# Square8_V1_2.net
KiCad netlist of a schematic drawn in EAGLE
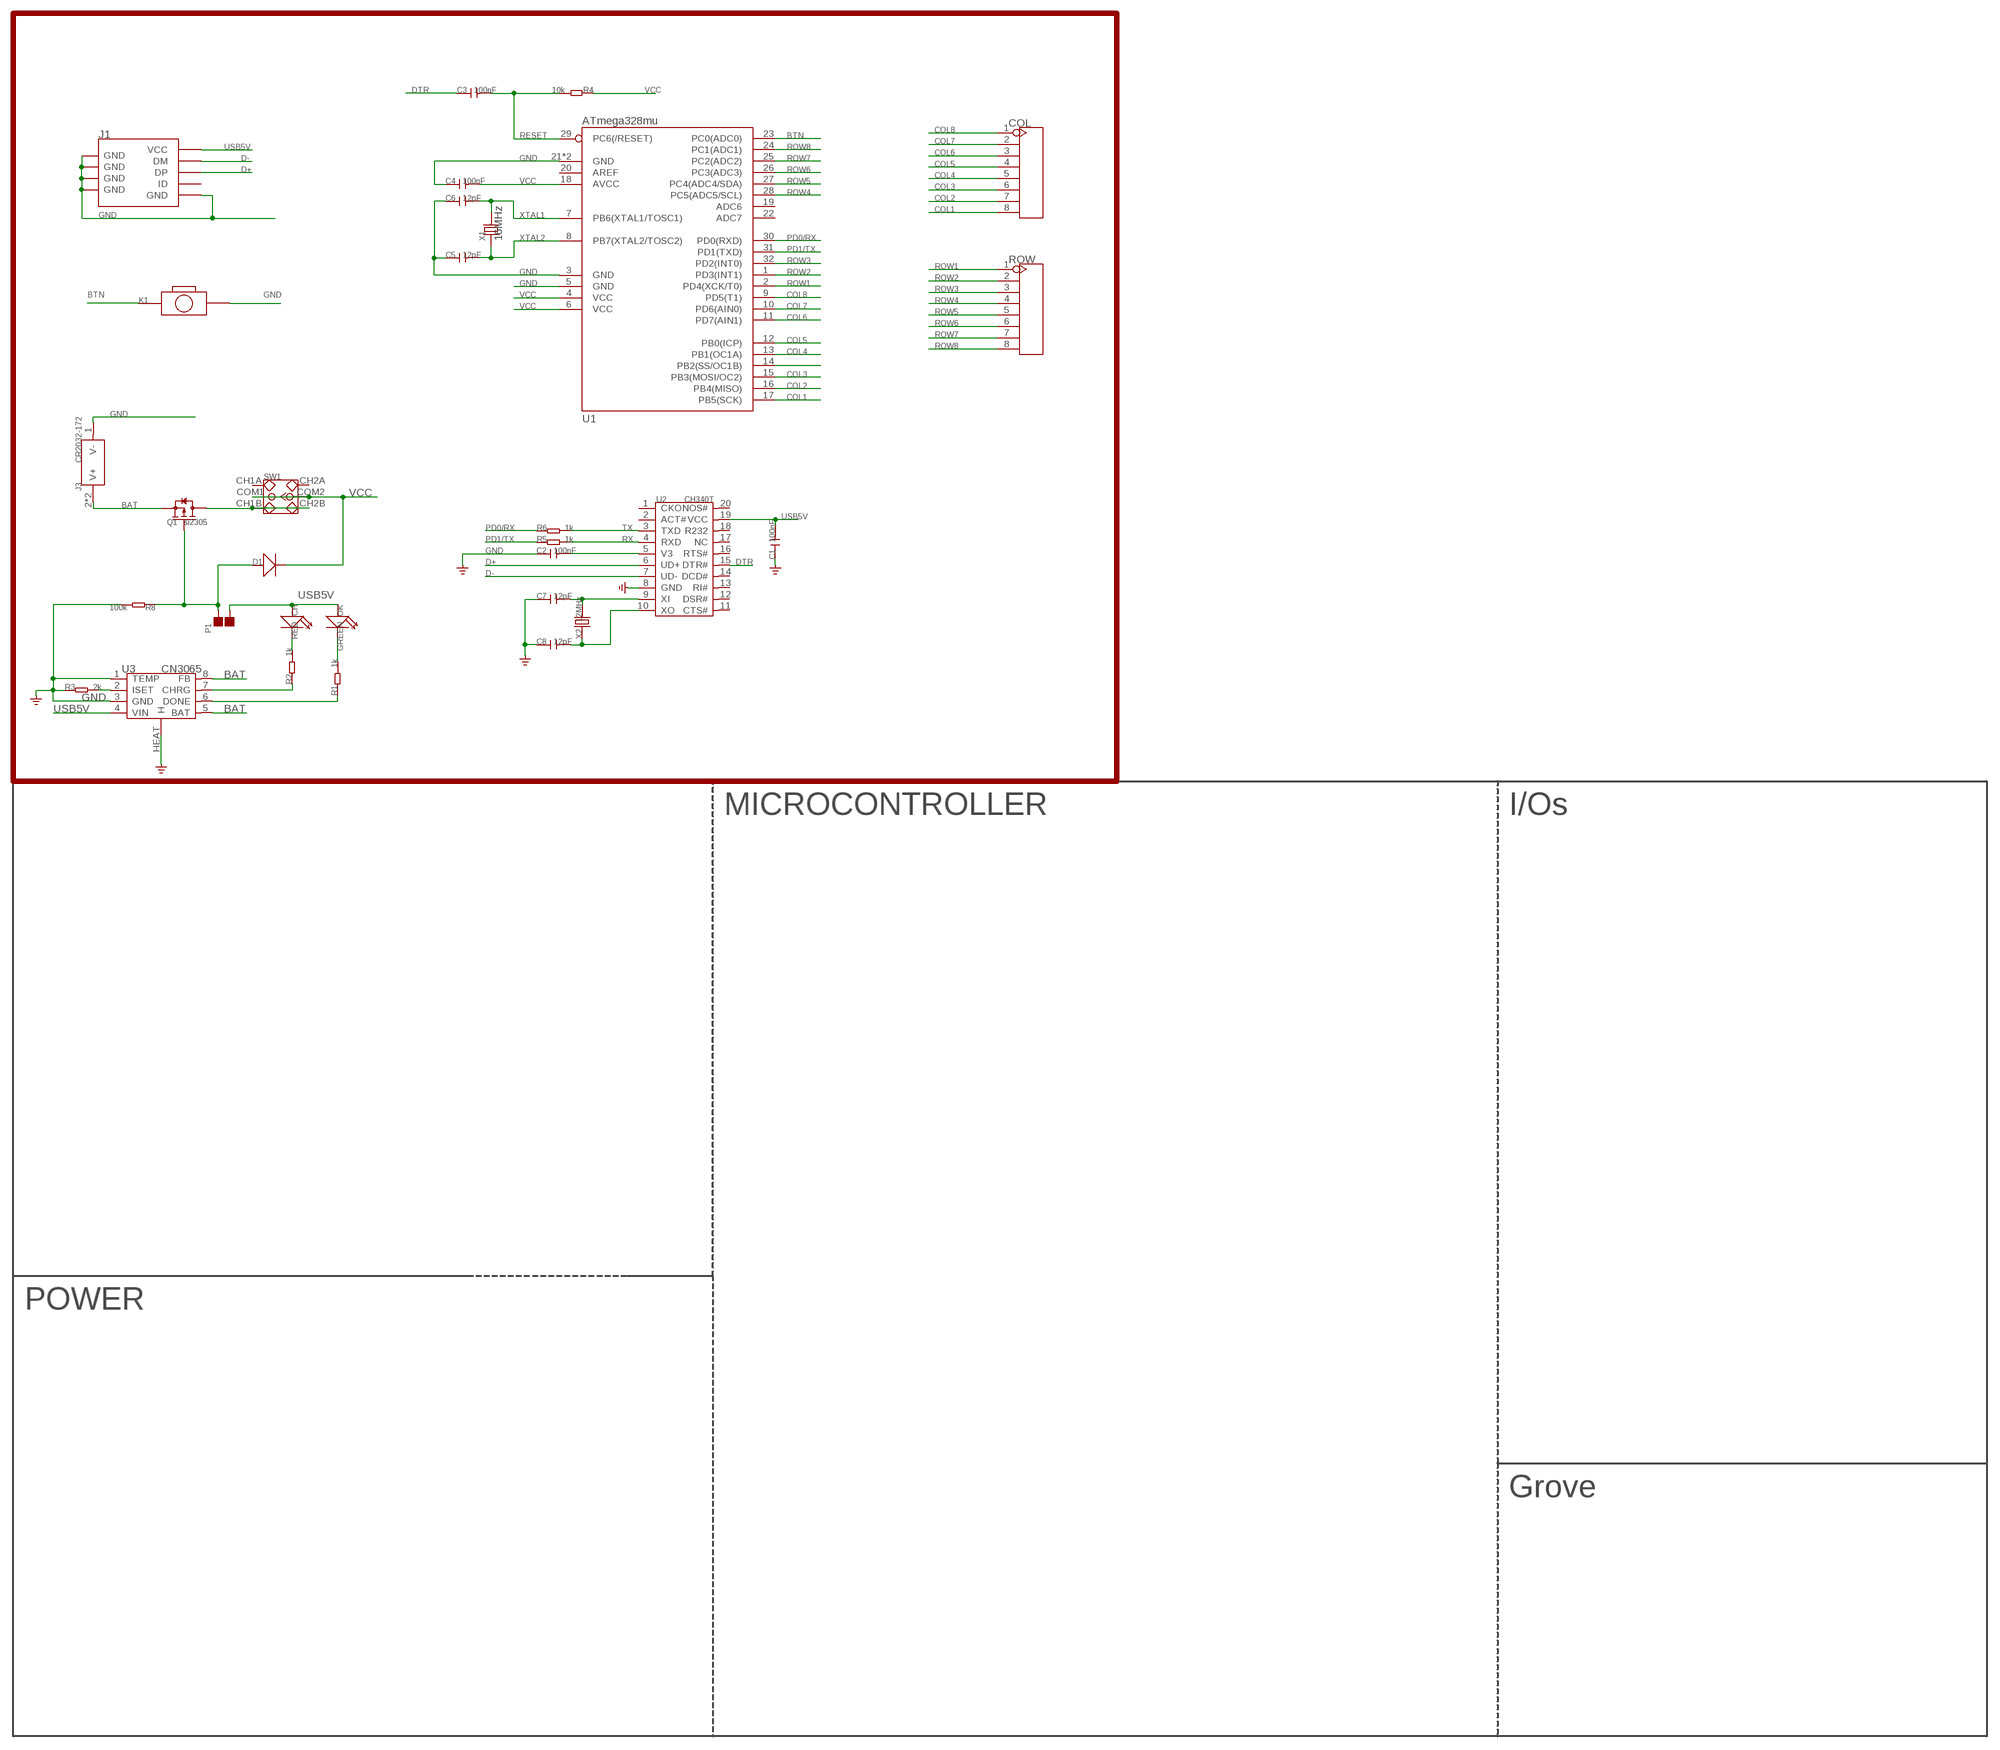
[diagram p0: schematic, sheet 1]

(export (version "E")
  (design (tool "Eeschema 10.0.6"))
  (components
    (comp (ref "C1")
      (value "100nF")
      (footprint "eagle-import:CERAMIC-2.54")
      (libsource (lib "eagle-import") (part "C'2.54'"))
    )
    (comp (ref "C2")
      (value "100nF")
      (footprint "eagle-import:CERAMIC-2.54")
      (libsource (lib "eagle-import") (part "C'2.54'"))
    )
    (comp (ref "C3")
      (value "100nF")
      (footprint "eagle-import:CERAMIC-2.54")
      (libsource (lib "eagle-import") (part "C'2.54'"))
    )
    (comp (ref "C4")
      (value "100nF")
      (footprint "eagle-import:CERAMIC-2.54")
      (libsource (lib "eagle-import") (part "C'2.54'"))
    )
    (comp (ref "C5")
      (value "12pF")
      (footprint "eagle-import:C0603")
      (libsource (lib "eagle-import") (part "C-0603"))
    )
    (comp (ref "C6")
      (value "12pF")
      (footprint "eagle-import:C0603")
      (libsource (lib "eagle-import") (part "C-0603"))
    )
    (comp (ref "C7")
      (value "12pF")
      (footprint "eagle-import:C0603")
      (libsource (lib "eagle-import") (part "C-0603"))
    )
    (comp (ref "C8")
      (value "12pF")
      (footprint "eagle-import:C0603")
      (libsource (lib "eagle-import") (part "C-0603"))
    )
    (comp (ref "CH")
      (value "RED")
      (footprint "eagle-import:LED-2P-2.54-3MM")
      (libsource (lib "eagle-import") (part "LED-3MM"))
    )
    (comp (ref "COL")
      (value "HEADER-8P-2.54")
      (footprint "eagle-import:8P-2.54")
      (libsource (lib "eagle-import") (part "HEADER-8P-2.54"))
    )
    (comp (ref "D1")
      (value "D'B130L-13-F'")
      (footprint "eagle-import:SMA")
      (libsource (lib "eagle-import") (part "D'B130L-13-F'"))
    )
    (comp (ref "J1")
      (value "USB-MINIUSB-5P-MICRO")
      (footprint "eagle-import:MICRO-USB")
      (libsource (lib "eagle-import") (part "USB-MINIUSB-5P-MICRO"))
    )
    (comp (ref "J3")
      (value "CR2032-172")
      (footprint "eagle-import:2032-D20-CIRCLE")
      (libsource (lib "eagle-import") (part "HOLDER-BAT-CIRCLE"))
    )
    (comp (ref "K1")
      (value "BUTTON-2P'TS-1101F'")
      (footprint "eagle-import:2P-3.4X6.0X3.55H-90D")
      (libsource (lib "eagle-import") (part "BUTTON-2P'TS-1101F'"))
    )
    (comp (ref "OK")
      (value "GREEN")
      (footprint "eagle-import:LED-2P-2.54-3MM")
      (libsource (lib "eagle-import") (part "LED-3MM"))
    )
    (comp (ref "P1")
      (value "PAD-JUMPER-2P")
      (footprint "eagle-import:2P-SMD-1.78X1.27")
      (fields (field (name "PARTNO") "DNP"))
      (libsource (lib "eagle-import") (part "PAD-JUMPER-2P"))
    )
    (comp (ref "Q1")
      (value "si2305")
      (footprint "eagle-import:SOT23")
      (libsource (lib "eagle-import") (part "MOSFET-P'SI2323CDS/SI2305DS{lt}BR{gt}'"))
    )
    (comp (ref "R1")
      (value "1k")
      (footprint "eagle-import:R0204_7")
      (libsource (lib "eagle-import") (part "R-0204/7"))
    )
    (comp (ref "R2")
      (value "1k")
      (footprint "eagle-import:R0204_7")
      (libsource (lib "eagle-import") (part "R-0204/7"))
    )
    (comp (ref "R3")
      (value "2k")
      (footprint "eagle-import:R0204_7")
      (libsource (lib "eagle-import") (part "R-0204/7"))
    )
    (comp (ref "R4")
      (value "10k")
      (footprint "eagle-import:R0204_7")
      (libsource (lib "eagle-import") (part "R-0204/7"))
    )
    (comp (ref "R5")
      (value "1k")
      (footprint "eagle-import:R0204_7")
      (libsource (lib "eagle-import") (part "R-0204/7"))
    )
    (comp (ref "R6")
      (value "1k")
      (footprint "eagle-import:R0204_7")
      (libsource (lib "eagle-import") (part "R-0204/7"))
    )
    (comp (ref "R8")
      (value "100k")
      (footprint "eagle-import:R0603")
      (libsource (lib "eagle-import") (part "R-0603"))
    )
    (comp (ref "ROW")
      (value "HEADER-8P-2.54")
      (footprint "eagle-import:8P-2.54")
      (libsource (lib "eagle-import") (part "HEADER-8P-2.54"))
    )
    (comp (ref "SW1")
      (value "SWITCH-2CH-6P'90D'")
      (footprint "eagle-import:6P-2CH-2.5-9.1X3.5X3.2H-90D")
      (libsource (lib "eagle-import") (part "SWITCH-2CH-6P'90D'"))
    )
    (comp (ref "U1")
      (value "ATmega328mu")
      (footprint "eagle-import:MLF32X-W_HEAT")
      (libsource (lib "eagle-import") (part "ATMEGA8/168/328MLF"))
    )
    (comp (ref "U2")
      (value "CH340T")
      (footprint "eagle-import:SSOP20")
      (libsource (lib "eagle-import") (part "CH340T"))
    )
    (comp (ref "U3")
      (value "CN3065")
      (footprint "eagle-import:DFN8")
      (libsource (lib "eagle-import") (part "CN3065"))
    )
    (comp (ref "X1")
      (value "16MHz")
      (footprint "eagle-import:HC49S")
      (libsource (lib "eagle-import") (part "CRYSTAL'HC49S'"))
    )
    (comp (ref "X2")
      (value "12MHz")
      (footprint "eagle-import:HC49S")
      (libsource (lib "eagle-import") (part "CRYSTAL'HC49S'"))
    )
  )
  (nets
    (net (code "1") (name "/BAT") (class "Default")
      (node (ref "J3") (pin "2") (pinfunction "V+_2") (pintype "bidirectional"))
      (node (ref "J3") (pin "3") (pinfunction "V+_3") (pintype "bidirectional"))
      (node (ref "Q1") (pin "2") (pinfunction "S_2") (pintype "passive"))
      (node (ref "U3") (pin "5") (pinfunction "BAT_5") (pintype "bidirectional"))
      (node (ref "U3") (pin "8") (pinfunction "FB_8") (pintype "input"))
    )
    (net (code "2") (name "/BTN") (class "Default")
      (node (ref "K1") (pin "P$1") (pinfunction "1_P$1") (pintype "bidirectional"))
      (node (ref "U1") (pin "23") (pinfunction "PC0(ADC0)_23") (pintype "bidirectional"))
    )
    (net (code "3") (name "/COL1") (class "Default")
      (node (ref "COL") (pin "8") (pinfunction "8_8") (pintype "bidirectional"))
      (node (ref "U1") (pin "17") (pinfunction "PB5(SCK)_17") (pintype "bidirectional"))
    )
    (net (code "4") (name "/COL2") (class "Default")
      (node (ref "COL") (pin "7") (pinfunction "7_7") (pintype "bidirectional"))
      (node (ref "U1") (pin "16") (pinfunction "PB4(MISO)_16") (pintype "bidirectional"))
    )
    (net (code "5") (name "/COL3") (class "Default")
      (node (ref "COL") (pin "6") (pinfunction "6_6") (pintype "bidirectional"))
      (node (ref "U1") (pin "15") (pinfunction "PB3(MOSI/OC2)_15") (pintype "bidirectional"))
    )
    (net (code "6") (name "/COL4") (class "Default")
      (node (ref "COL") (pin "5") (pinfunction "5_5") (pintype "bidirectional"))
      (node (ref "U1") (pin "13") (pinfunction "PB1(OC1A)_13") (pintype "bidirectional"))
    )
    (net (code "7") (name "/COL5") (class "Default")
      (node (ref "COL") (pin "4") (pinfunction "4_4") (pintype "bidirectional"))
      (node (ref "U1") (pin "12") (pinfunction "PB0(ICP)_12") (pintype "bidirectional"))
    )
    (net (code "8") (name "/COL6") (class "Default")
      (node (ref "COL") (pin "3") (pinfunction "3_3") (pintype "bidirectional"))
      (node (ref "U1") (pin "11") (pinfunction "PD7(AIN1)_11") (pintype "bidirectional"))
    )
    (net (code "9") (name "/COL7") (class "Default")
      (node (ref "COL") (pin "2") (pinfunction "2_2") (pintype "bidirectional"))
      (node (ref "U1") (pin "10") (pinfunction "PD6(AIN0)_10") (pintype "bidirectional"))
    )
    (net (code "10") (name "/COL8") (class "Default")
      (node (ref "COL") (pin "1") (pinfunction "1_1") (pintype "bidirectional"))
      (node (ref "U1") (pin "9") (pinfunction "PD5(T1)_9") (pintype "bidirectional"))
    )
    (net (code "11") (name "/D+") (class "Default")
      (node (ref "J1") (pin "3") (pinfunction "DP_3") (pintype "bidirectional"))
      (node (ref "U2") (pin "6") (pinfunction "UD+_6") (pintype "bidirectional"))
    )
    (net (code "12") (name "/D-") (class "Default")
      (node (ref "J1") (pin "2") (pinfunction "DM_2") (pintype "bidirectional"))
      (node (ref "U2") (pin "7") (pinfunction "UD-_7") (pintype "bidirectional"))
    )
    (net (code "13") (name "/DTR") (class "Default")
      (node (ref "C3") (pin "1") (pinfunction "1_1") (pintype "passive"))
      (node (ref "U2") (pin "15") (pinfunction "DTR#_15") (pintype "output"))
    )
    (net (code "14") (name "/NOS#") (class "Default")
      (node (ref "U2") (pin "20") (pinfunction "NOS#_20") (pintype "power_in"))
    )
    (net (code "15") (name "/PD0{slash}RX") (class "Default")
      (node (ref "R6") (pin "1") (pinfunction "1_1") (pintype "passive"))
      (node (ref "U1") (pin "30") (pinfunction "PD0(RXD)_30") (pintype "bidirectional"))
    )
    (net (code "16") (name "/PD1{slash}TX") (class "Default")
      (node (ref "R5") (pin "1") (pinfunction "1_1") (pintype "passive"))
      (node (ref "U1") (pin "31") (pinfunction "PD1(TXD)_31") (pintype "bidirectional"))
    )
    (net (code "17") (name "/RESET") (class "Default")
      (node (ref "C3") (pin "2") (pinfunction "2_2") (pintype "passive"))
      (node (ref "R4") (pin "2") (pinfunction "2_2") (pintype "passive"))
      (node (ref "U1") (pin "29") (pinfunction "PC6(/RESET)_29") (pintype "bidirectional"))
    )
    (net (code "18") (name "/ROW1") (class "Default")
      (node (ref "ROW") (pin "1") (pinfunction "1_1") (pintype "bidirectional"))
      (node (ref "U1") (pin "2") (pinfunction "PD4(XCK/T0)_2") (pintype "bidirectional"))
    )
    (net (code "19") (name "/ROW2") (class "Default")
      (node (ref "ROW") (pin "2") (pinfunction "2_2") (pintype "bidirectional"))
      (node (ref "U1") (pin "1") (pinfunction "PD3(INT1)_1") (pintype "bidirectional"))
    )
    (net (code "20") (name "/ROW3") (class "Default")
      (node (ref "ROW") (pin "3") (pinfunction "3_3") (pintype "bidirectional"))
      (node (ref "U1") (pin "32") (pinfunction "PD2(INT0)_32") (pintype "bidirectional"))
    )
    (net (code "21") (name "/ROW4") (class "Default")
      (node (ref "ROW") (pin "4") (pinfunction "4_4") (pintype "bidirectional"))
      (node (ref "U1") (pin "28") (pinfunction "PC5(ADC5/SCL)_28") (pintype "bidirectional"))
    )
    (net (code "22") (name "/ROW5") (class "Default")
      (node (ref "ROW") (pin "5") (pinfunction "5_5") (pintype "bidirectional"))
      (node (ref "U1") (pin "27") (pinfunction "PC4(ADC4/SDA)_27") (pintype "bidirectional"))
    )
    (net (code "23") (name "/ROW6") (class "Default")
      (node (ref "ROW") (pin "6") (pinfunction "6_6") (pintype "bidirectional"))
      (node (ref "U1") (pin "26") (pinfunction "PC3(ADC3)_26") (pintype "bidirectional"))
    )
    (net (code "24") (name "/ROW7") (class "Default")
      (node (ref "ROW") (pin "7") (pinfunction "7_7") (pintype "bidirectional"))
      (node (ref "U1") (pin "25") (pinfunction "PC2(ADC2)_25") (pintype "bidirectional"))
    )
    (net (code "25") (name "/ROW8") (class "Default")
      (node (ref "ROW") (pin "8") (pinfunction "8_8") (pintype "bidirectional"))
      (node (ref "U1") (pin "24") (pinfunction "PC1(ADC1)_24") (pintype "bidirectional"))
    )
    (net (code "26") (name "/RX") (class "Default")
      (node (ref "R5") (pin "2") (pinfunction "2_2") (pintype "passive"))
      (node (ref "U2") (pin "4") (pinfunction "RXD_4") (pintype "input"))
    )
    (net (code "27") (name "/TX") (class "Default")
      (node (ref "R6") (pin "2") (pinfunction "2_2") (pintype "passive"))
      (node (ref "U2") (pin "3") (pinfunction "TXD_3") (pintype "output"))
    )
    (net (code "28") (name "/USB5V") (class "Default")
      (node (ref "C1") (pin "2") (pinfunction "2_2") (pintype "passive"))
      (node (ref "CH") (pin "A") (pinfunction "+_A") (pintype "passive"))
      (node (ref "J1") (pin "1") (pinfunction "VCC_1") (pintype "bidirectional"))
      (node (ref "OK") (pin "A") (pinfunction "+_A") (pintype "passive"))
      (node (ref "P1") (pin "1") (pinfunction "1_1") (pintype "bidirectional"))
      (node (ref "U2") (pin "19") (pinfunction "VCC_19") (pintype "power_in"))
      (node (ref "U3") (pin "4") (pinfunction "VIN_4") (pintype "input"))
    )
    (net (code "29") (name "/VCC") (class "Default")
      (node (ref "C4") (pin "2") (pinfunction "2_2") (pintype "passive"))
      (node (ref "D1") (pin "1") (pinfunction "-_1") (pintype "passive"))
      (node (ref "R4") (pin "1") (pinfunction "1_1") (pintype "passive"))
      (node (ref "SW1") (pin "COM1") (pinfunction "COM1_COM1") (pintype "bidirectional"))
      (node (ref "SW1") (pin "COM2") (pinfunction "COM2_COM2") (pintype "bidirectional"))
      (node (ref "U1") (pin "18") (pinfunction "AVCC_18") (pintype "bidirectional"))
      (node (ref "U1") (pin "4") (pinfunction "VCC_4") (pintype "bidirectional"))
      (node (ref "U1") (pin "6") (pinfunction "VCC_6") (pintype "bidirectional"))
    )
    (net (code "30") (name "/XTAL1") (class "Default")
      (node (ref "C6") (pin "2") (pinfunction "2_2") (pintype "passive"))
      (node (ref "U1") (pin "7") (pinfunction "PB6(XTAL1/TOSC1)_7") (pintype "bidirectional"))
      (node (ref "X1") (pin "2") (pinfunction "2_2") (pintype "passive"))
    )
    (net (code "31") (name "/XTAL2") (class "Default")
      (node (ref "C5") (pin "2") (pinfunction "2_2") (pintype "passive"))
      (node (ref "U1") (pin "8") (pinfunction "PB7(XTAL2/TOSC2)_8") (pintype "bidirectional"))
      (node (ref "X1") (pin "1") (pinfunction "1_1") (pintype "passive"))
    )
    (net (code "32") (name "GND_POWER") (class "Default")
      (node (ref "C1") (pin "1") (pinfunction "1_1") (pintype "passive"))
      (node (ref "C2") (pin "1") (pinfunction "1_1") (pintype "passive"))
      (node (ref "C4") (pin "1") (pinfunction "1_1") (pintype "passive"))
      (node (ref "C5") (pin "1") (pinfunction "1_1") (pintype "passive"))
      (node (ref "C6") (pin "1") (pinfunction "1_1") (pintype "passive"))
      (node (ref "C7") (pin "1") (pinfunction "1_1") (pintype "passive"))
      (node (ref "C8") (pin "1") (pinfunction "1_1") (pintype "passive"))
      (node (ref "J1") (pin "5") (pinfunction "GND_5") (pintype "bidirectional"))
      (node (ref "J1") (pin "S1") (pinfunction "GND_S1") (pintype "bidirectional"))
      (node (ref "J1") (pin "S2") (pinfunction "GND_S2") (pintype "bidirectional"))
      (node (ref "J1") (pin "S3") (pinfunction "GND_S3") (pintype "bidirectional"))
      (node (ref "J1") (pin "S4") (pinfunction "GND_S4") (pintype "bidirectional"))
      (node (ref "J1") (pin "S5") (pinfunction "GND_S5") (pintype "bidirectional"))
      (node (ref "J1") (pin "S6") (pinfunction "GND_S6") (pintype "bidirectional"))
      (node (ref "J3") (pin "1") (pinfunction "V-_1") (pintype "bidirectional"))
      (node (ref "K1") (pin "P$2") (pinfunction "2_P$2") (pintype "bidirectional"))
      (node (ref "R3") (pin "1") (pinfunction "1_1") (pintype "passive"))
      (node (ref "R8") (pin "2") (pinfunction "2_2") (pintype "passive"))
      (node (ref "U1") (pin "21") (pinfunction "GND_21") (pintype "bidirectional"))
      (node (ref "U1") (pin "3") (pinfunction "GND_3") (pintype "bidirectional"))
      (node (ref "U1") (pin "5") (pinfunction "GND_5") (pintype "bidirectional"))
      (node (ref "U1") (pin "HEAT") (pinfunction "GND_HEAT") (pintype "bidirectional"))
      (node (ref "U2") (pin "8") (pinfunction "GND_8") (pintype "power_in"))
      (node (ref "U3") (pin "1") (pinfunction "TEMP_1") (pintype "input"))
      (node (ref "U3") (pin "3") (pinfunction "GND_3") (pintype "power_in"))
      (node (ref "U3") (pin "HEAT") (pinfunction "H_HEAT") (pintype "bidirectional"))
    )
    (net (code "33") (name "Net-(CH--)") (class "Default")
      (node (ref "CH") (pin "K") (pinfunction "-_K") (pintype "passive"))
      (node (ref "R2") (pin "2") (pinfunction "2_2") (pintype "passive"))
    )
    (net (code "34") (name "Net-(D1-+)") (class "Default")
      (node (ref "D1") (pin "2") (pinfunction "+_2") (pintype "passive"))
      (node (ref "P1") (pin "2") (pinfunction "2_2") (pintype "bidirectional"))
      (node (ref "Q1") (pin "1") (pinfunction "G_1") (pintype "passive"))
      (node (ref "R8") (pin "1") (pinfunction "1_1") (pintype "passive"))
    )
    (net (code "35") (name "Net-(OK--)") (class "Default")
      (node (ref "OK") (pin "K") (pinfunction "-_K") (pintype "passive"))
      (node (ref "R1") (pin "2") (pinfunction "2_2") (pintype "passive"))
    )
    (net (code "36") (name "Net-(Q1-D)") (class "Default")
      (node (ref "Q1") (pin "3") (pinfunction "D_3") (pintype "passive"))
      (node (ref "SW1") (pin "CH1B") (pinfunction "CH1B_CH1B") (pintype "bidirectional"))
      (node (ref "SW1") (pin "CH2B") (pinfunction "CH2B_CH2B") (pintype "bidirectional"))
    )
    (net (code "37") (name "Net-(U2-V3)") (class "Default")
      (node (ref "C2") (pin "2") (pinfunction "2_2") (pintype "passive"))
      (node (ref "U2") (pin "5") (pinfunction "V3_5") (pintype "power_in"))
    )
    (net (code "38") (name "Net-(U2-XI)") (class "Default")
      (node (ref "C7") (pin "2") (pinfunction "2_2") (pintype "passive"))
      (node (ref "U2") (pin "9") (pinfunction "XI_9") (pintype "input"))
      (node (ref "X2") (pin "2") (pinfunction "2_2") (pintype "passive"))
    )
    (net (code "39") (name "Net-(U2-XO)") (class "Default")
      (node (ref "C8") (pin "2") (pinfunction "2_2") (pintype "passive"))
      (node (ref "U2") (pin "10") (pinfunction "XO_10") (pintype "output"))
      (node (ref "X2") (pin "1") (pinfunction "1_1") (pintype "passive"))
    )
    (net (code "40") (name "Net-(U3-CHRG)") (class "Default")
      (node (ref "R2") (pin "1") (pinfunction "1_1") (pintype "passive"))
      (node (ref "U3") (pin "7") (pinfunction "CHRG_7") (pintype "bidirectional"))
    )
    (net (code "41") (name "Net-(U3-DONE)") (class "Default")
      (node (ref "R1") (pin "1") (pinfunction "1_1") (pintype "passive"))
      (node (ref "U3") (pin "6") (pinfunction "DONE_6") (pintype "bidirectional"))
    )
    (net (code "42") (name "Net-(U3-ISET)") (class "Default")
      (node (ref "R3") (pin "2") (pinfunction "2_2") (pintype "passive"))
      (node (ref "U3") (pin "2") (pinfunction "ISET_2") (pintype "bidirectional"))
    )
    (net (code "43") (name "unconnected-(J1-ID-Pad4)") (class "Default")
      (node (ref "J1") (pin "4") (pinfunction "ID_4") (pintype "bidirectional"))
    )
    (net (code "44") (name "unconnected-(SW1-PadCH1A)") (class "Default")
      (node (ref "SW1") (pin "CH1A") (pinfunction "CH1A_CH1A") (pintype "bidirectional"))
    )
    (net (code "45") (name "unconnected-(SW1-PadCH2A)") (class "Default")
      (node (ref "SW1") (pin "CH2A") (pinfunction "CH2A_CH2A") (pintype "bidirectional"))
    )
    (net (code "46") (name "unconnected-(U1-ADC6-Pad19)") (class "Default")
      (node (ref "U1") (pin "19") (pinfunction "ADC6_19") (pintype "bidirectional"))
    )
    (net (code "47") (name "unconnected-(U1-ADC7-Pad22)") (class "Default")
      (node (ref "U1") (pin "22") (pinfunction "ADC7_22") (pintype "bidirectional"))
    )
    (net (code "48") (name "unconnected-(U1-AREF-Pad20)") (class "Default")
      (node (ref "U1") (pin "20") (pinfunction "AREF_20") (pintype "bidirectional"))
    )
    (net (code "49") (name "unconnected-(U1-PB2(SS{slash}OC1B)-Pad14)") (class "Default")
      (node (ref "U1") (pin "14") (pinfunction "PB2(SS/OC1B)_14") (pintype "bidirectional"))
    )
    (net (code "50") (name "unconnected-(U2-ACT#-Pad2)") (class "Default")
      (node (ref "U2") (pin "2") (pinfunction "ACT#_2") (pintype "output"))
    )
    (net (code "51") (name "unconnected-(U2-CKO-Pad1)") (class "Default")
      (node (ref "U2") (pin "1") (pinfunction "CKO_1") (pintype "output"))
    )
    (net (code "52") (name "unconnected-(U2-CTS#-Pad11)") (class "Default")
      (node (ref "U2") (pin "11") (pinfunction "CTS#_11") (pintype "input"))
    )
    (net (code "53") (name "unconnected-(U2-DCD#-Pad14)") (class "Default")
      (node (ref "U2") (pin "14") (pinfunction "DCD#_14") (pintype "input"))
    )
    (net (code "54") (name "unconnected-(U2-DSR#-Pad12)") (class "Default")
      (node (ref "U2") (pin "12") (pinfunction "DSR#_12") (pintype "input"))
    )
    (net (code "55") (name "unconnected-(U2-NC-Pad17)") (class "Default")
      (node (ref "U2") (pin "17") (pinfunction "NC_17") (pintype "no_connect"))
    )
    (net (code "56") (name "unconnected-(U2-R232-Pad18)") (class "Default")
      (node (ref "U2") (pin "18") (pinfunction "R232_18") (pintype "input"))
    )
    (net (code "57") (name "unconnected-(U2-RI#-Pad13)") (class "Default")
      (node (ref "U2") (pin "13") (pinfunction "RI#_13") (pintype "input"))
    )
    (net (code "58") (name "unconnected-(U2-RTS#-Pad16)") (class "Default")
      (node (ref "U2") (pin "16") (pinfunction "RTS#_16") (pintype "output"))
    )
  )
)
